# LED_Driver_NF2W757GT-F1.net
KiCad netlist of a schematic drawn in Altium Designer
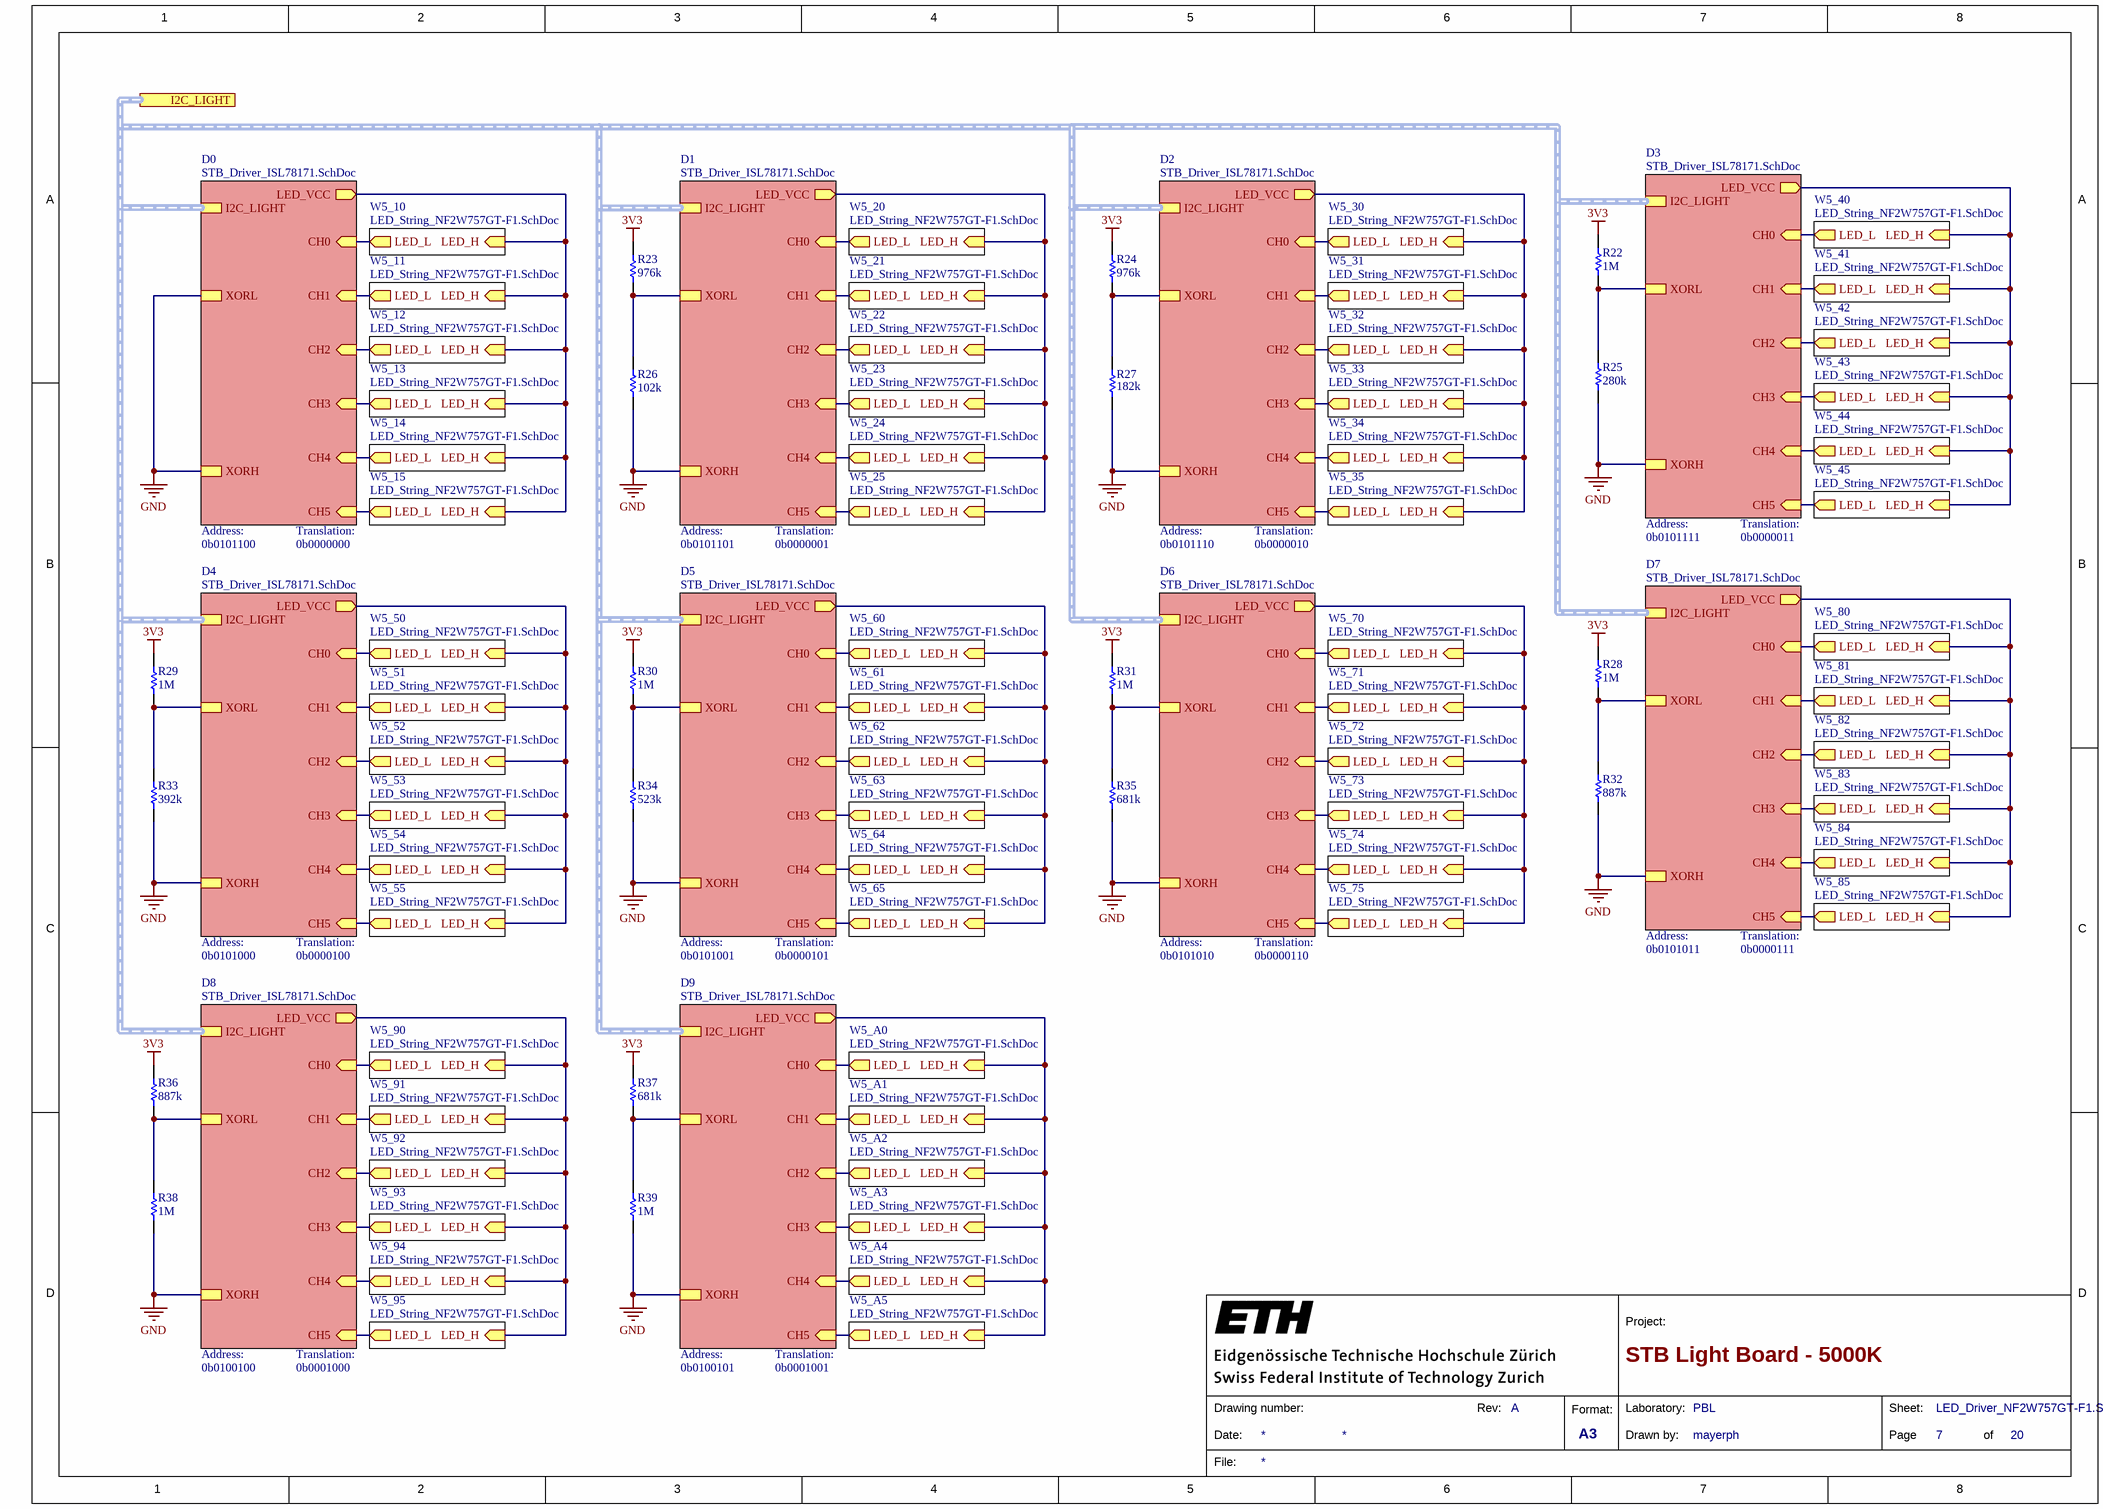
[diagram p0: LED_Driver_NF2W757GT-F1.SchDoc]

(export (version "E")
  (design (tool "Eeschema 10.0.6"))
  (components
    (comp (ref "R22")
      (value "1M")
      (footprint "RESC1005X40X25LL05T05")
      (description "Chip Resistor, 1 MOhm, +/- 1%, 100 mW, -55 to 155 degC, 0402 (1005 Metric), RoHS, Tape and Reel")
      (fields (field (name "PARTNUMBER") "ERJ-2RKF1004X") (field (name "TOLERANCE") "1%"))
      (libsource (lib "Altium Content Vault") (part "RES-2"))
    )
    (comp (ref "R23")
      (value "976k")
      (footprint "RESC1005X40X25LL05T05")
      (fields
        (field (name "MANUFACTURER") "Panasonic")
        (field (name "PART NUMBER") "ERJ-2RKF9763X")
        (field (name "TOLERANCE") "1%")
      )
      (libsource (lib "Altium Content Vault") (part "RES"))
    )
    (comp (ref "R24")
      (value "976k")
      (footprint "RESC1005X40X25LL05T05")
      (fields
        (field (name "MANUFACTURER") "Panasonic")
        (field (name "PART NUMBER") "ERJ-2RKF9763X")
        (field (name "TOLERANCE") "1%")
      )
      (libsource (lib "Altium Content Vault") (part "RES"))
    )
    (comp (ref "R25")
      (value "280k")
      (footprint "RESC1005X40X25LL05T05")
      (description "Chip Resistor, 280 KOhm, +/- 1%, 100 mW, -55 to 155 degC, 0402 (1005 Metric), RoHS, Cut Tape")
      (fields (field (name "PARTNUMBER") "ERJ-2RKF2803X") (field (name "MANUFACTURER") "Basic Passives"))
      (libsource (lib "Altium Content Vault") (part "RES-2"))
    )
    (comp (ref "R26")
      (value "102k")
      (footprint "RESC1005X40X25LL05T05")
      (fields
        (field (name "MANUFACTURER") "Panasonic")
        (field (name "PART NUMBER") "ERJ-2RKF1023X")
        (field (name "TOLERANCE") "1%")
      )
      (libsource (lib "Altium Content Vault") (part "RES"))
    )
    (comp (ref "R27")
      (value "182k")
      (footprint "RESC1005X40X25LL05T05")
      (fields
        (field (name "MANUFACTURER") "Vishay Dale")
        (field (name "PART NUMBER") "CRCW0402182KFKED")
        (field (name "TOLERANCE") "1%")
      )
      (libsource (lib "Altium Content Vault") (part "RES"))
    )
    (comp (ref "R28")
      (value "1M")
      (footprint "RESC1005X40X25LL05T05")
      (description "Chip Resistor, 1 MOhm, +/- 1%, 100 mW, -55 to 155 degC, 0402 (1005 Metric), RoHS, Tape and Reel")
      (fields (field (name "PARTNUMBER") "ERJ-2RKF1004X") (field (name "TOLERANCE") "1%"))
      (libsource (lib "Altium Content Vault") (part "RES-2"))
    )
    (comp (ref "R29")
      (value "1M")
      (footprint "RESC1005X40X25LL05T05")
      (description "Chip Resistor, 1 MOhm, +/- 1%, 100 mW, -55 to 155 degC, 0402 (1005 Metric), RoHS, Tape and Reel")
      (fields (field (name "PARTNUMBER") "ERJ-2RKF1004X") (field (name "TOLERANCE") "1%"))
      (libsource (lib "Altium Content Vault") (part "RES-2"))
    )
    (comp (ref "R30")
      (value "1M")
      (footprint "RESC1005X40X25LL05T05")
      (description "Chip Resistor, 1 MOhm, +/- 1%, 100 mW, -55 to 155 degC, 0402 (1005 Metric), RoHS, Tape and Reel")
      (fields (field (name "PARTNUMBER") "ERJ-2RKF1004X") (field (name "TOLERANCE") "1%"))
      (libsource (lib "Altium Content Vault") (part "RES-2"))
    )
    (comp (ref "R31")
      (value "1M")
      (footprint "RESC1005X40X25LL05T05")
      (description "Chip Resistor, 1 MOhm, +/- 1%, 100 mW, -55 to 155 degC, 0402 (1005 Metric), RoHS, Tape and Reel")
      (fields (field (name "PARTNUMBER") "ERJ-2RKF1004X") (field (name "TOLERANCE") "1%"))
      (libsource (lib "Altium Content Vault") (part "RES-2"))
    )
    (comp (ref "R32")
      (value "887k")
      (footprint "RESC1005X40X25LL05T10")
      (fields
        (field (name "PART NUMBER") "RC0402FR-07887KL")
        (field (name "MANUFACTURER") "Yageo / Phycomp")
        (field (name "TOLERANCE") "1%")
      )
      (libsource (lib "Altium Content Vault") (part "RES"))
    )
    (comp (ref "R33")
      (value "392k")
      (footprint "RESC1005X40X25LL05T05")
      (fields
        (field (name "PART NUMBER") "ERJ-2RKF3923X")
        (field (name "MANUFACTURER") "Panasonic")
        (field (name "TOLERANCE") "1%")
      )
      (libsource (lib "Altium Content Vault") (part "RES"))
    )
    (comp (ref "R34")
      (value "523k")
      (footprint "RESC1005X40X25LL05T05")
      (fields
        (field (name "MANUFACTURER") "Panasonic")
        (field (name "PART NUMBER") "ERJ-2RKF5233X")
        (field (name "TOLERANCE") "1%")
      )
      (libsource (lib "Altium Content Vault") (part "RES"))
    )
    (comp (ref "R35")
      (value "681k")
      (footprint "RESC1005X40X25LL05T05")
      (fields
        (field (name "MANUFACTURER") "Panasonic")
        (field (name "PART NUMBER") "ERJ-2RKF6813X")
        (field (name "TOLERANCE") "1%")
      )
      (libsource (lib "Altium Content Vault") (part "RES"))
    )
    (comp (ref "R36")
      (value "887k")
      (footprint "RESC1005X40X25LL05T10")
      (fields
        (field (name "PART NUMBER") "RC0402FR-07887KL")
        (field (name "MANUFACTURER") "Yageo / Phycomp")
        (field (name "TOLERANCE") "1%")
      )
      (libsource (lib "Altium Content Vault") (part "RES"))
    )
    (comp (ref "R37")
      (value "681k")
      (footprint "RESC1005X40X25LL05T05")
      (fields
        (field (name "MANUFACTURER") "Panasonic")
        (field (name "PART NUMBER") "ERJ-2RKF6813X")
        (field (name "TOLERANCE") "1%")
      )
      (libsource (lib "Altium Content Vault") (part "RES"))
    )
    (comp (ref "R38")
      (value "1M")
      (footprint "RESC1005X40X25LL05T05")
      (description "Chip Resistor, 1 MOhm, +/- 1%, 100 mW, -55 to 155 degC, 0402 (1005 Metric), RoHS, Tape and Reel")
      (fields (field (name "PARTNUMBER") "ERJ-2RKF1004X") (field (name "TOLERANCE") "1%"))
      (libsource (lib "Altium Content Vault") (part "RES-2"))
    )
    (comp (ref "R39")
      (value "1M")
      (footprint "RESC1005X40X25LL05T05")
      (description "Chip Resistor, 1 MOhm, +/- 1%, 100 mW, -55 to 155 degC, 0402 (1005 Metric), RoHS, Tape and Reel")
      (fields (field (name "PARTNUMBER") "ERJ-2RKF1004X") (field (name "TOLERANCE") "1%"))
      (libsource (lib "Altium Content Vault") (part "RES-2"))
    )
  )
  (nets
    (net (code "73") (name "/XORL") (class "Default")
      (node (ref "R22") (pin "1") (pinfunction "1_1") (pintype "passive"))
      (node (ref "R25") (pin "2") (pinfunction "2_2") (pintype "passive"))
    )
    (net (code "74") (name "/XORL_1") (class "Default")
      (node (ref "R36") (pin "1") (pinfunction "1_1") (pintype "passive"))
      (node (ref "R38") (pin "2") (pinfunction "2_2") (pintype "passive"))
    )
    (net (code "75") (name "/XORL_2") (class "Default")
      (node (ref "R37") (pin "1") (pinfunction "1_1") (pintype "passive"))
      (node (ref "R39") (pin "2") (pinfunction "2_2") (pintype "passive"))
    )
    (net (code "76") (name "/XORL_3") (class "Default")
      (node (ref "R29") (pin "1") (pinfunction "1_1") (pintype "passive"))
      (node (ref "R33") (pin "2") (pinfunction "2_2") (pintype "passive"))
    )
    (net (code "77") (name "/XORL_4") (class "Default")
      (node (ref "R30") (pin "1") (pinfunction "1_1") (pintype "passive"))
      (node (ref "R34") (pin "2") (pinfunction "2_2") (pintype "passive"))
    )
    (net (code "78") (name "/XORL_5") (class "Default")
      (node (ref "R23") (pin "1") (pinfunction "1_1") (pintype "passive"))
      (node (ref "R26") (pin "2") (pinfunction "2_2") (pintype "passive"))
    )
    (net (code "79") (name "/XORL_6") (class "Default")
      (node (ref "R24") (pin "1") (pinfunction "1_1") (pintype "passive"))
      (node (ref "R27") (pin "2") (pinfunction "2_2") (pintype "passive"))
    )
    (net (code "80") (name "/XORL_7") (class "Default")
      (node (ref "R31") (pin "1") (pinfunction "1_1") (pintype "passive"))
      (node (ref "R35") (pin "2") (pinfunction "2_2") (pintype "passive"))
    )
    (net (code "81") (name "/XORL_8") (class "Default")
      (node (ref "R28") (pin "1") (pinfunction "1_1") (pintype "passive"))
      (node (ref "R32") (pin "2") (pinfunction "2_2") (pintype "passive"))
    )
    (net (code "82") (name "3V3") (class "Default")
      (node (ref "R22") (pin "2") (pinfunction "2_2") (pintype "passive"))
      (node (ref "R23") (pin "2") (pinfunction "2_2") (pintype "passive"))
      (node (ref "R24") (pin "2") (pinfunction "2_2") (pintype "passive"))
      (node (ref "R28") (pin "2") (pinfunction "2_2") (pintype "passive"))
      (node (ref "R29") (pin "2") (pinfunction "2_2") (pintype "passive"))
      (node (ref "R30") (pin "2") (pinfunction "2_2") (pintype "passive"))
      (node (ref "R31") (pin "2") (pinfunction "2_2") (pintype "passive"))
      (node (ref "R36") (pin "2") (pinfunction "2_2") (pintype "passive"))
      (node (ref "R37") (pin "2") (pinfunction "2_2") (pintype "passive"))
    )
    (net (code "83") (name "GND") (class "Default")
      (node (ref "R25") (pin "1") (pinfunction "1_1") (pintype "passive"))
      (node (ref "R26") (pin "1") (pinfunction "1_1") (pintype "passive"))
      (node (ref "R27") (pin "1") (pinfunction "1_1") (pintype "passive"))
      (node (ref "R32") (pin "1") (pinfunction "1_1") (pintype "passive"))
      (node (ref "R33") (pin "1") (pinfunction "1_1") (pintype "passive"))
      (node (ref "R34") (pin "1") (pinfunction "1_1") (pintype "passive"))
      (node (ref "R35") (pin "1") (pinfunction "1_1") (pintype "passive"))
      (node (ref "R38") (pin "1") (pinfunction "1_1") (pintype "passive"))
      (node (ref "R39") (pin "1") (pinfunction "1_1") (pintype "passive"))
    )
  )
)
